# SCH_05_WCT_RLD.net
KiCad netlist of a schematic drawn in Altium Designer
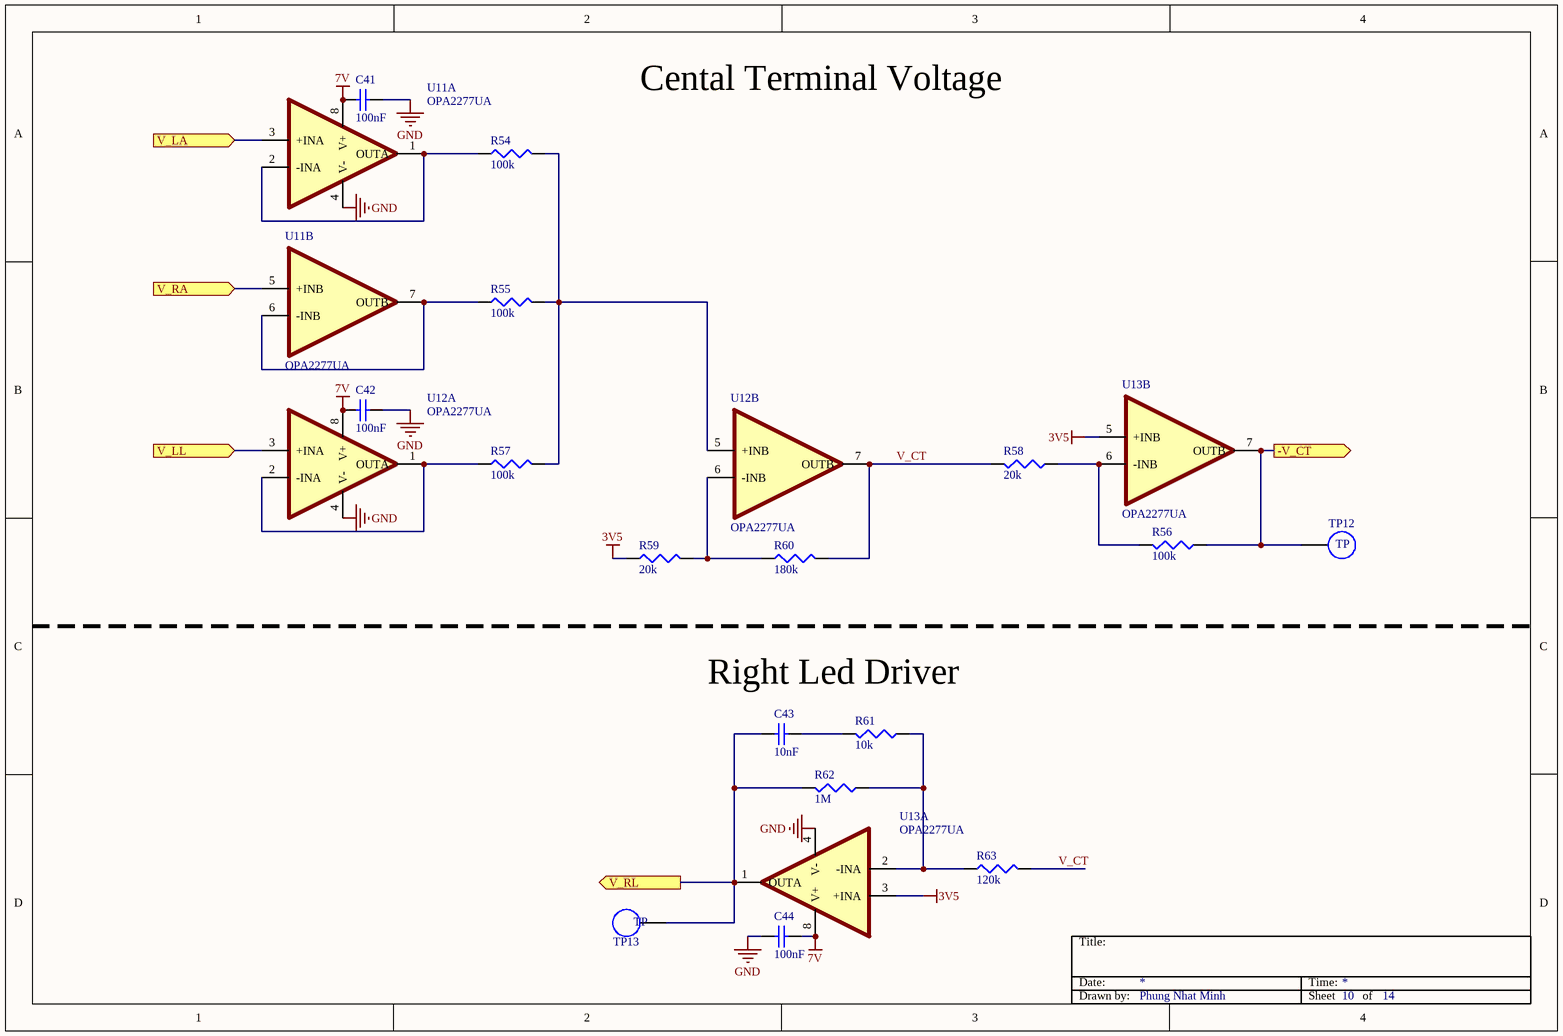
[diagram p0: SCH_05_WCT_RLD.SchDoc]

(export (version "E")
  (design (tool "Eeschema 10.0.6"))
  (components
    (comp (ref "C41")
      (value "100nF")
      (footprint "WCAP-CSGP_0603_L1.6W0.8H0.8_Reflow")
      (description "WCAP-CSGP Multilayer Ceramic Chip Capacitor, General Purpose, size 0603, X7R, 100nF, 50VDC")
      (fields
        (field (name "MANUFACTURER PART NUMBER") "885012206095")
        (field (name "MANUFACTURER") "Wurth Elektronik")
      )
      (libsource (lib "Altium_WCAP-CSGP (rev24b)") (part "885012206095"))
    )
    (comp (ref "C42")
      (value "100nF")
      (footprint "WCAP-CSGP_0603_L1.6W0.8H0.8_Reflow")
      (description "WCAP-CSGP Multilayer Ceramic Chip Capacitor, General Purpose, size 0603, X7R, 100nF, 50VDC")
      (fields
        (field (name "MANUFACTURER PART NUMBER") "885012206095")
        (field (name "MANUFACTURER") "Wurth Elektronik")
      )
      (libsource (lib "Altium_WCAP-CSGP (rev24b)") (part "885012206095"))
    )
    (comp (ref "C43")
      (value "10nF")
      (footprint "WCAP-CSGP_0603_L1.6W0.8H0.8_Reflow")
      (description "WCAP-CSGP Multilayer Ceramic Chip Capacitor, General Purpose, size 0603, X7R, 10nF, 50VDC")
      (fields
        (field (name "MANUFACTURER PART NUMBER") "885012206089")
        (field (name "MANUFACTURER") "Wurth Elektronik")
      )
      (libsource (lib "Altium_WCAP-CSGP (rev24b)") (part "885012206089"))
    )
    (comp (ref "C44")
      (value "100nF")
      (footprint "WCAP-CSGP_0603_L1.6W0.8H0.8_Reflow")
      (description "WCAP-CSGP Multilayer Ceramic Chip Capacitor, General Purpose, size 0603, X7R, 100nF, 50VDC")
      (fields
        (field (name "MANUFACTURER PART NUMBER") "885012206095")
        (field (name "MANUFACTURER") "Wurth Elektronik")
      )
      (libsource (lib "Altium_WCAP-CSGP (rev24b)") (part "885012206095"))
    )
    (comp (ref "R54")
      (value "100k")
      (footprint "WRIS-PSMB_0603_L1.6W0.8H0.35")
      (description "WRIS-PSMB Metal Plate Resistor, SMT, size 0603, 0.33W, 5mΩ, +/-1%")
      (fields
        (field (name "MANUFACTURER PART NUMBER") "580060716001")
        (field (name "MANUFACTURER") "Wurth Elektronik")
      )
      (libsource (lib "Altium_WRIS-PSMB (rev22a)") (part "580060716001"))
    )
    (comp (ref "R55")
      (value "100k")
      (footprint "WRIS-PSMB_0603_L1.6W0.8H0.35")
      (description "WRIS-PSMB Metal Plate Resistor, SMT, size 0603, 0.33W, 5mΩ, +/-1%")
      (fields
        (field (name "MANUFACTURER PART NUMBER") "580060716001")
        (field (name "MANUFACTURER") "Wurth Elektronik")
      )
      (libsource (lib "Altium_WRIS-PSMB (rev22a)") (part "580060716001"))
    )
    (comp (ref "R56")
      (value "100k")
      (footprint "WRIS-PSMB_0603_L1.6W0.8H0.35")
      (description "WRIS-PSMB Metal Plate Resistor, SMT, size 0603, 0.33W, 5mΩ, +/-1%")
      (fields
        (field (name "MANUFACTURER PART NUMBER") "580060716001")
        (field (name "MANUFACTURER") "Wurth Elektronik")
      )
      (libsource (lib "Altium_WRIS-PSMB (rev22a)") (part "580060716001"))
    )
    (comp (ref "R57")
      (value "100k")
      (footprint "WRIS-PSMB_0603_L1.6W0.8H0.35")
      (description "WRIS-PSMB Metal Plate Resistor, SMT, size 0603, 0.33W, 5mΩ, +/-1%")
      (fields
        (field (name "MANUFACTURER PART NUMBER") "580060716001")
        (field (name "MANUFACTURER") "Wurth Elektronik")
      )
      (libsource (lib "Altium_WRIS-PSMB (rev22a)") (part "580060716001"))
    )
    (comp (ref "R58")
      (value "20k")
      (footprint "WRIS-PSMB_0603_L1.6W0.8H0.35")
      (description "WRIS-PSMB Metal Plate Resistor, SMT, size 0603, 0.33W, 5mΩ, +/-1%")
      (fields
        (field (name "MANUFACTURER PART NUMBER") "580060716001")
        (field (name "MANUFACTURER") "Wurth Elektronik")
      )
      (libsource (lib "Altium_WRIS-PSMB (rev22a)") (part "580060716001"))
    )
    (comp (ref "R59")
      (value "20k")
      (footprint "WRIS-PSMB_0603_L1.6W0.8H0.35")
      (description "WRIS-PSMB Metal Plate Resistor, SMT, size 0603, 0.33W, 5mΩ, +/-1%")
      (fields
        (field (name "MANUFACTURER PART NUMBER") "580060716001")
        (field (name "MANUFACTURER") "Wurth Elektronik")
      )
      (libsource (lib "Altium_WRIS-PSMB (rev22a)") (part "580060716001"))
    )
    (comp (ref "R60")
      (value "180k")
      (footprint "WRIS-PSMB_0603_L1.6W0.8H0.35")
      (description "WRIS-PSMB Metal Plate Resistor, SMT, size 0603, 0.33W, 5mΩ, +/-1%")
      (fields
        (field (name "MANUFACTURER PART NUMBER") "580060716001")
        (field (name "MANUFACTURER") "Wurth Elektronik")
      )
      (libsource (lib "Altium_WRIS-PSMB (rev22a)") (part "580060716001"))
    )
    (comp (ref "R61")
      (value "10k")
      (footprint "WRIS-PSMB_0603_L1.6W0.8H0.35")
      (description "WRIS-PSMB Metal Plate Resistor, SMT, size 0603, 0.33W, 5mΩ, +/-1%")
      (fields
        (field (name "MANUFACTURER PART NUMBER") "580060716001")
        (field (name "MANUFACTURER") "Wurth Elektronik")
      )
      (libsource (lib "Altium_WRIS-PSMB (rev22a)") (part "580060716001"))
    )
    (comp (ref "R62")
      (value "1M")
      (footprint "WRIS-PSMB_0603_L1.6W0.8H0.35")
      (description "WRIS-PSMB Metal Plate Resistor, SMT, size 0603, 0.33W, 5mΩ, +/-1%")
      (fields
        (field (name "MANUFACTURER PART NUMBER") "580060716001")
        (field (name "MANUFACTURER") "Wurth Elektronik")
      )
      (libsource (lib "Altium_WRIS-PSMB (rev22a)") (part "580060716001"))
    )
    (comp (ref "R63")
      (value "120k")
      (footprint "WRIS-PSMB_0603_L1.6W0.8H0.35")
      (description "WRIS-PSMB Metal Plate Resistor, SMT, size 0603, 0.33W, 5mΩ, +/-1%")
      (fields
        (field (name "MANUFACTURER PART NUMBER") "580060716001")
        (field (name "MANUFACTURER") "Wurth Elektronik")
      )
      (libsource (lib "Altium_WRIS-PSMB (rev22a)") (part "580060716001"))
    )
    (comp (ref "TP12")
      (value "Pad_Test_Point")
      (footprint "Pad_Test_Point")
      (libsource (lib "Test_Point") (part "Pad_Test_Point"))
    )
    (comp (ref "TP13")
      (value "Pad_Test_Point")
      (footprint "Pad_Test_Point")
      (libsource (lib "Test_Point") (part "Pad_Test_Point"))
    )
    (comp (ref "U11")
      (value "OPA2277UA")
      (footprint "SOIC127P599X175-8N")
      (fields (field (name "MP") "OPA2227UA"))
      (libsource (lib "OPA2277") (part "OPA2277UA"))
    )
    (comp (ref "U12")
      (value "OPA2277UA")
      (footprint "SOIC127P599X175-8N")
      (fields (field (name "MP") "OPA2227UA"))
      (libsource (lib "OPA2277") (part "OPA2277UA"))
    )
    (comp (ref "U13")
      (value "OPA2277UA")
      (footprint "SOIC127P599X175-8N")
      (fields (field (name "MP") "OPA2227UA"))
      (libsource (lib "OPA2277") (part "OPA2277UA"))
    )
  )
  (nets
    (net (code "1") (name "/-V_CT") (class "Default")
      (node (ref "R56") (pin "2") (pinfunction "2_2") (pintype "passive"))
      (node (ref "TP12") (pin "1") (pinfunction "1_1") (pintype "passive"))
      (node (ref "U13") (pin "7") (pinfunction "OUTB_7") (pintype "passive"))
    )
    (net (code "2") (name "/V_CT") (class "Default")
      (node (ref "R58") (pin "1") (pinfunction "1_1") (pintype "passive"))
      (node (ref "R60") (pin "2") (pinfunction "2_2") (pintype "passive"))
      (node (ref "R63") (pin "2") (pinfunction "2_2") (pintype "passive"))
      (node (ref "U12") (pin "7") (pinfunction "OUTB_7") (pintype "passive"))
    )
    (net (code "3") (name "/V_LA") (class "Default")
      (node (ref "U11") (pin "3") (pinfunction "+INA_3") (pintype "passive"))
    )
    (net (code "4") (name "/V_LL") (class "Default")
      (node (ref "U12") (pin "3") (pinfunction "+INA_3") (pintype "passive"))
    )
    (net (code "5") (name "/V_RA") (class "Default")
      (node (ref "U11") (pin "5") (pinfunction "+INB_5") (pintype "passive"))
    )
    (net (code "6") (name "/V_RL") (class "Default")
      (node (ref "C43") (pin "2") (pinfunction "2_2") (pintype "passive"))
      (node (ref "R62") (pin "2") (pinfunction "2_2") (pintype "passive"))
      (node (ref "TP13") (pin "1") (pinfunction "1_1") (pintype "passive"))
      (node (ref "U13") (pin "1") (pinfunction "OUTA_1") (pintype "passive"))
    )
    (net (code "7") (name "3V5") (class "Default")
      (node (ref "R59") (pin "1") (pinfunction "1_1") (pintype "passive"))
      (node (ref "U13") (pin "3") (pinfunction "+INA_3") (pintype "passive"))
      (node (ref "U13") (pin "5") (pinfunction "+INB_5") (pintype "passive"))
    )
    (net (code "8") (name "7V") (class "Default")
      (node (ref "C41") (pin "2") (pinfunction "2_2") (pintype "passive"))
      (node (ref "C42") (pin "2") (pinfunction "2_2") (pintype "passive"))
      (node (ref "C44") (pin "2") (pinfunction "2_2") (pintype "passive"))
      (node (ref "U11") (pin "8") (pinfunction "V+_8") (pintype "power_in"))
      (node (ref "U12") (pin "8") (pinfunction "V+_8") (pintype "power_in"))
      (node (ref "U13") (pin "8") (pinfunction "V+_8") (pintype "power_in"))
    )
    (net (code "9") (name "GND") (class "Default")
      (node (ref "C41") (pin "1") (pinfunction "1_1") (pintype "passive"))
      (node (ref "C42") (pin "1") (pinfunction "1_1") (pintype "passive"))
      (node (ref "C44") (pin "1") (pinfunction "1_1") (pintype "passive"))
      (node (ref "U11") (pin "4") (pinfunction "V-_4") (pintype "power_in"))
      (node (ref "U12") (pin "4") (pinfunction "V-_4") (pintype "power_in"))
      (node (ref "U13") (pin "4") (pinfunction "V-_4") (pintype "power_in"))
    )
    (net (code "10") (name "Net-(C43-Pad1)") (class "Default")
      (node (ref "C43") (pin "1") (pinfunction "1_1") (pintype "passive"))
      (node (ref "R61") (pin "2") (pinfunction "2_2") (pintype "passive"))
    )
    (net (code "11") (name "Net-(U11A--INA)") (class "Default")
      (node (ref "R54") (pin "1") (pinfunction "1_1") (pintype "passive"))
      (node (ref "U11") (pin "1") (pinfunction "OUTA_1") (pintype "passive"))
      (node (ref "U11") (pin "2") (pinfunction "-INA_2") (pintype "passive"))
    )
    (net (code "12") (name "Net-(U11B--INB)") (class "Default")
      (node (ref "R55") (pin "1") (pinfunction "1_1") (pintype "passive"))
      (node (ref "U11") (pin "6") (pinfunction "-INB_6") (pintype "passive"))
      (node (ref "U11") (pin "7") (pinfunction "OUTB_7") (pintype "passive"))
    )
    (net (code "13") (name "Net-(U12A--INA)") (class "Default")
      (node (ref "R57") (pin "1") (pinfunction "1_1") (pintype "passive"))
      (node (ref "U12") (pin "1") (pinfunction "OUTA_1") (pintype "passive"))
      (node (ref "U12") (pin "2") (pinfunction "-INA_2") (pintype "passive"))
    )
    (net (code "14") (name "Net-(U12B-+INB)") (class "Default")
      (node (ref "R54") (pin "2") (pinfunction "2_2") (pintype "passive"))
      (node (ref "R55") (pin "2") (pinfunction "2_2") (pintype "passive"))
      (node (ref "R57") (pin "2") (pinfunction "2_2") (pintype "passive"))
      (node (ref "U12") (pin "5") (pinfunction "+INB_5") (pintype "passive"))
    )
    (net (code "15") (name "Net-(U12B--INB)") (class "Default")
      (node (ref "R59") (pin "2") (pinfunction "2_2") (pintype "passive"))
      (node (ref "R60") (pin "1") (pinfunction "1_1") (pintype "passive"))
      (node (ref "U12") (pin "6") (pinfunction "-INB_6") (pintype "passive"))
    )
    (net (code "16") (name "Net-(U13A--INA)") (class "Default")
      (node (ref "R61") (pin "1") (pinfunction "1_1") (pintype "passive"))
      (node (ref "R62") (pin "1") (pinfunction "1_1") (pintype "passive"))
      (node (ref "R63") (pin "1") (pinfunction "1_1") (pintype "passive"))
      (node (ref "U13") (pin "2") (pinfunction "-INA_2") (pintype "passive"))
    )
    (net (code "17") (name "Net-(U13B--INB)") (class "Default")
      (node (ref "R56") (pin "1") (pinfunction "1_1") (pintype "passive"))
      (node (ref "R58") (pin "2") (pinfunction "2_2") (pintype "passive"))
      (node (ref "U13") (pin "6") (pinfunction "-INB_6") (pintype "passive"))
    )
  )
)
